# MonoPedal.net
KiCad netlist of a schematic drawn in EAGLE
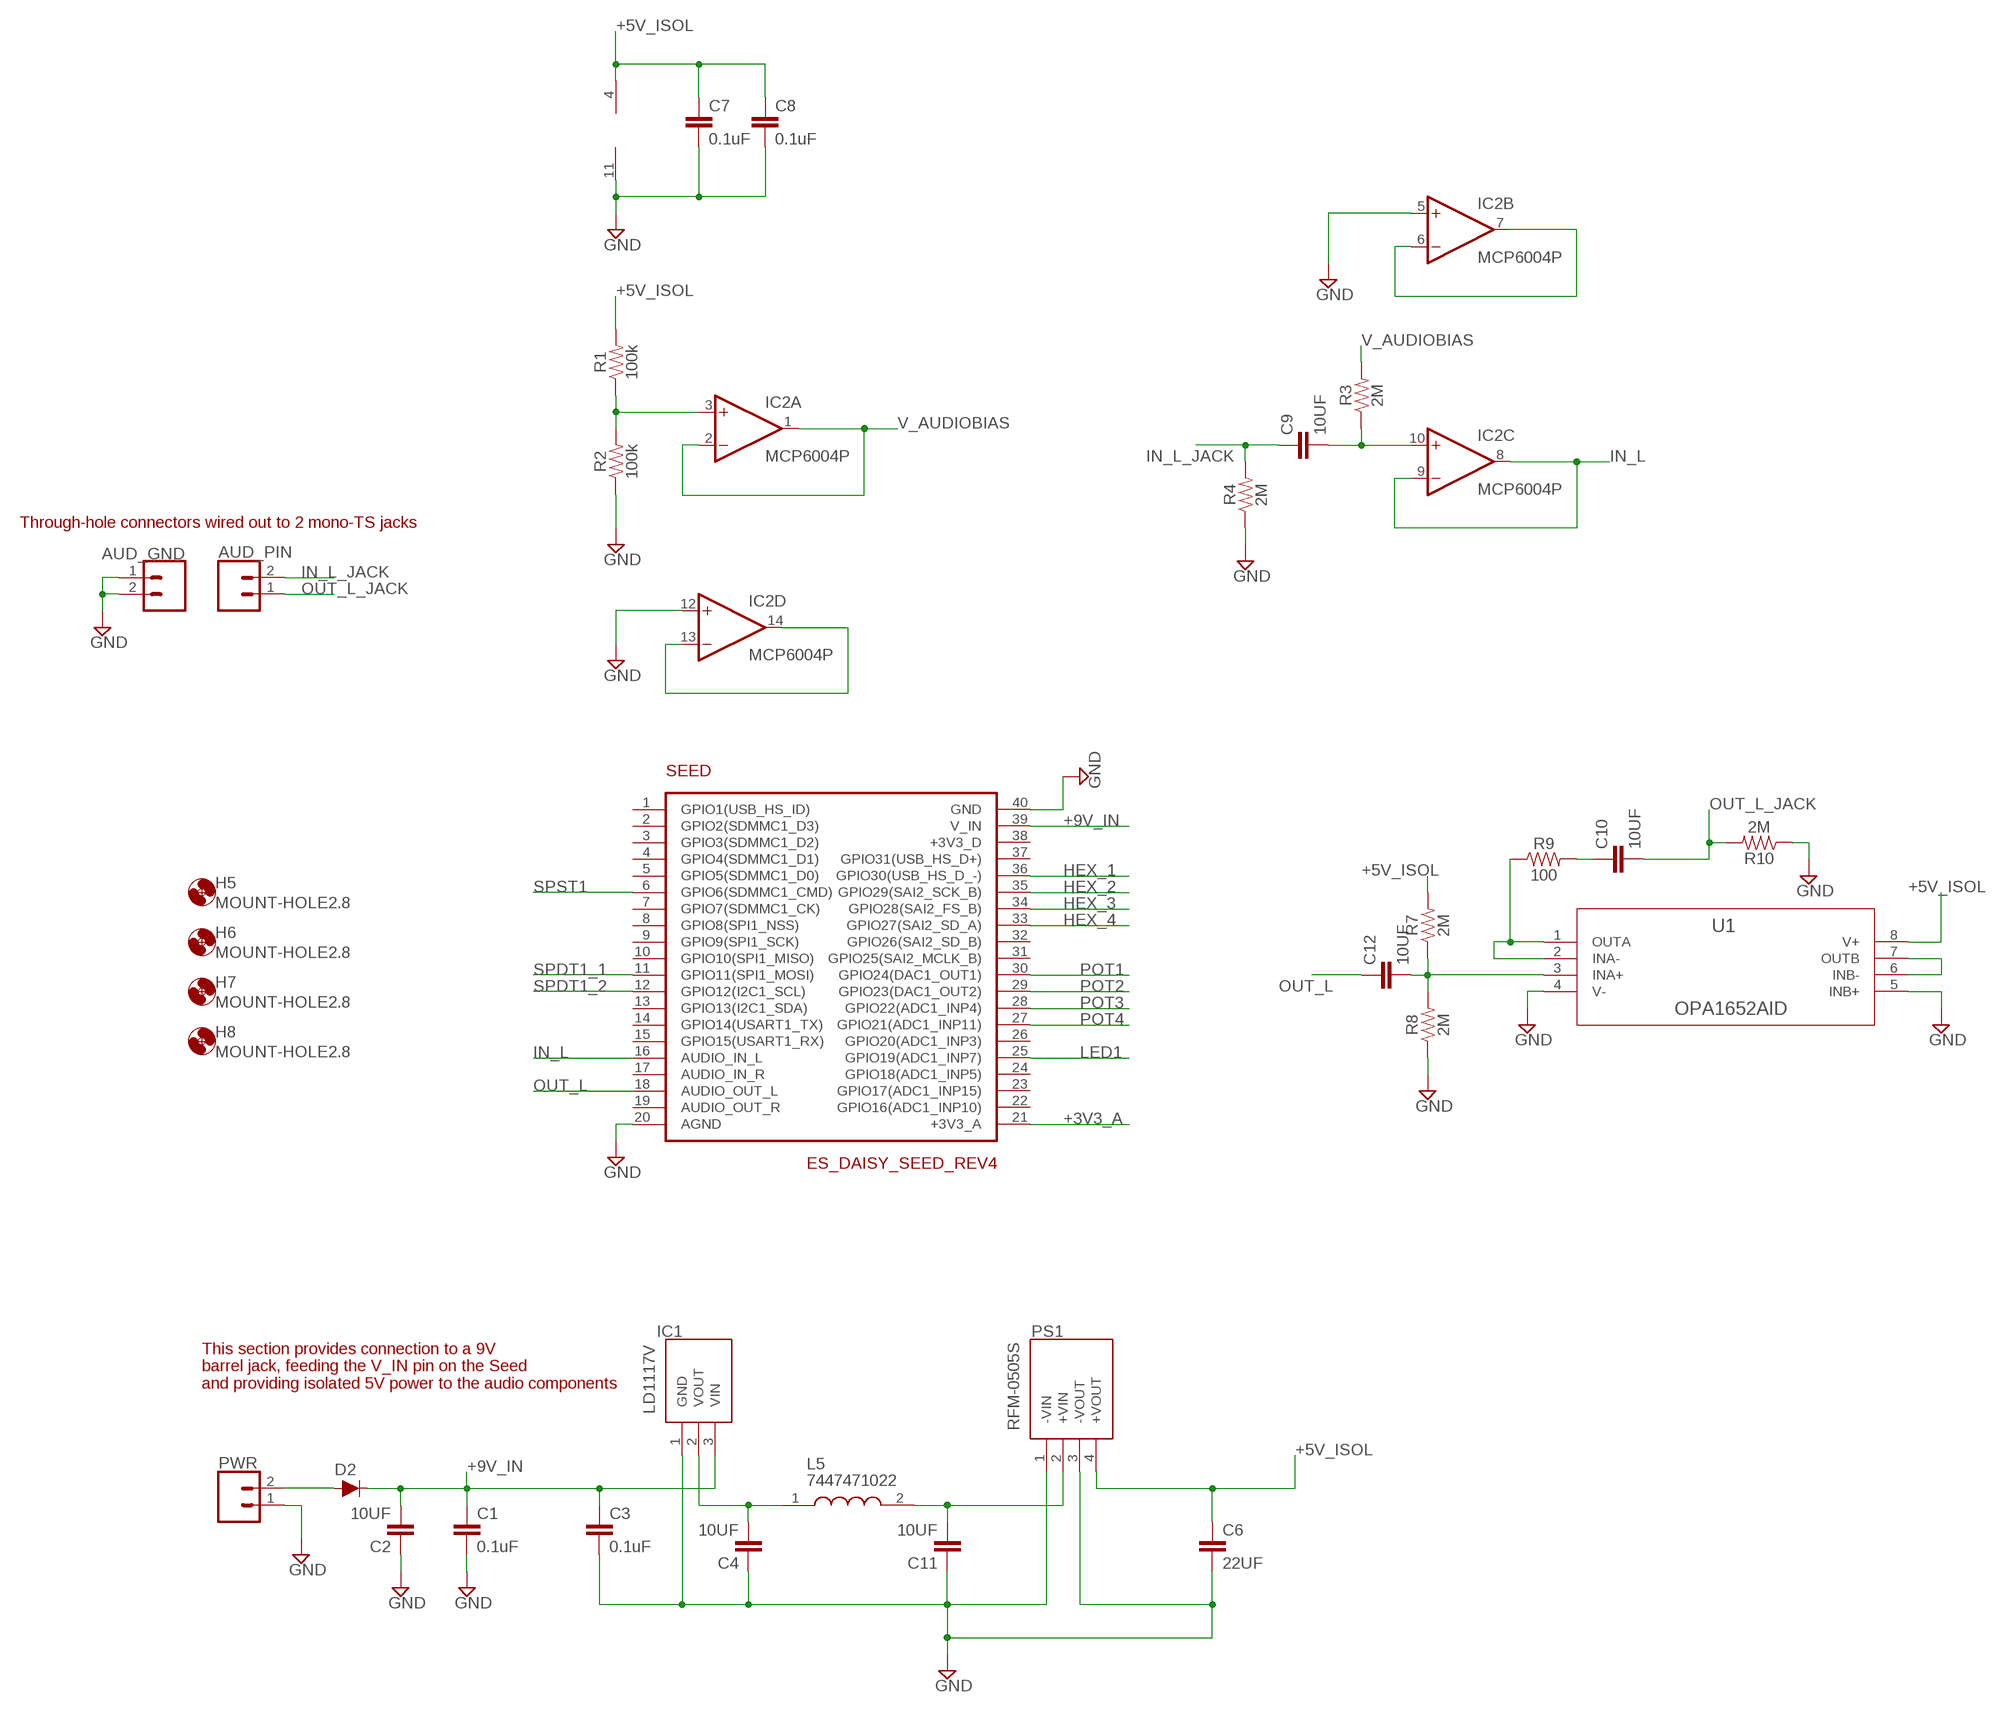
[diagram p0: schematic, sheet 1]
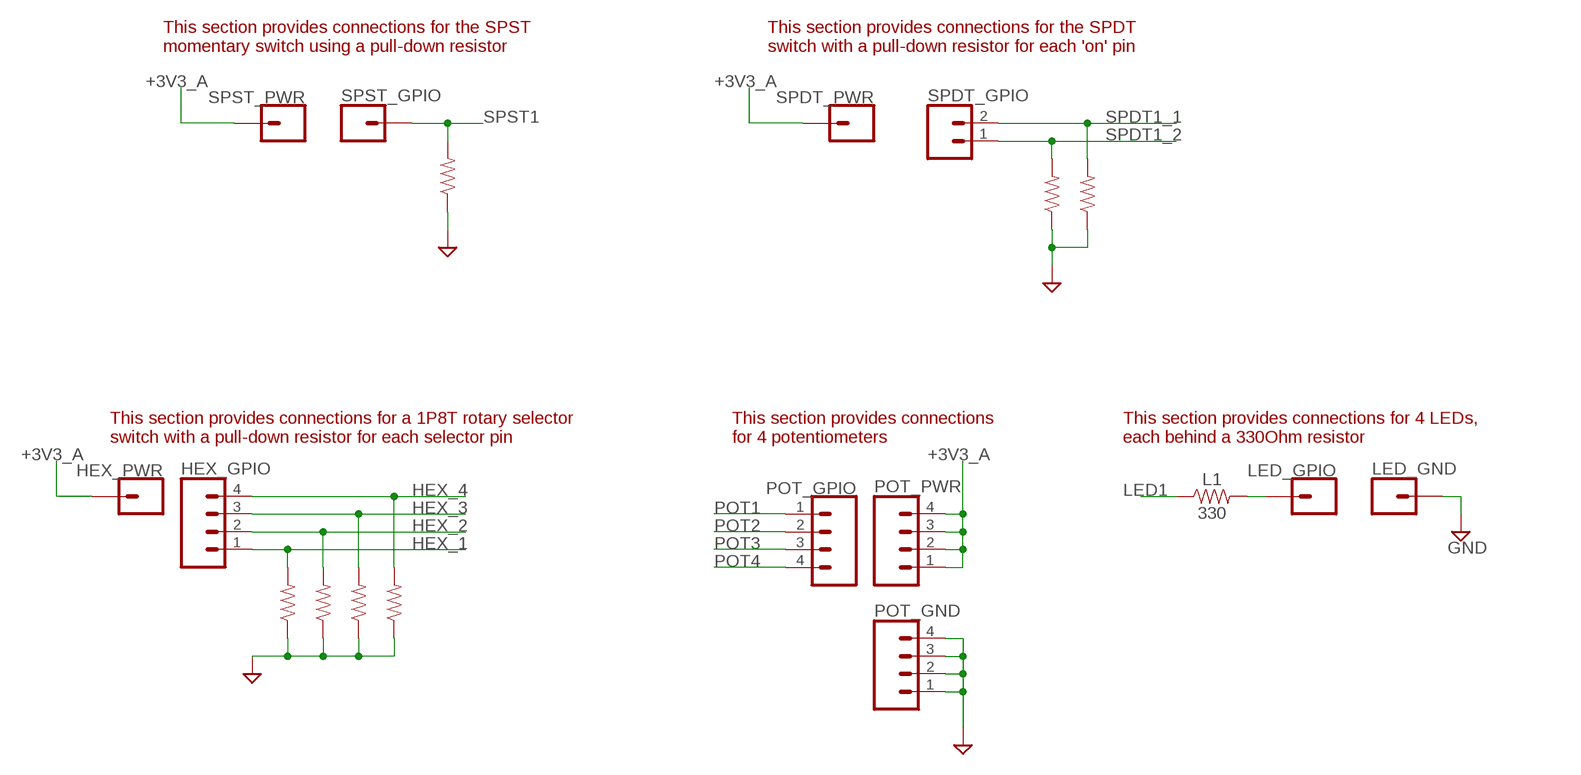
[diagram p1: schematic, sheet 2]

(export (version "E")
  (design (tool "Eeschema 10.0.6"))
  (components
    (comp (ref "AUD_GND")
      (value "CONN_02")
      (footprint "eagle-import:1X02")
      (libsource (lib "eagle-import") (part "CONN_02"))
    )
    (comp (ref "AUD_PIN")
      (value "CONN_02")
      (footprint "eagle-import:1X02")
      (libsource (lib "eagle-import") (part "CONN_02"))
    )
    (comp (ref "C1")
      (value "0.1uF")
      (footprint "eagle-import:CAP-PTH-SMALL-KIT")
      (libsource (lib "eagle-import") (part "0.1UF-KIT-EZ-50V-20%"))
    )
    (comp (ref "C2")
      (value "10UF")
      (footprint "eagle-import:CAP-PTH-SMALL-KIT")
      (libsource (lib "eagle-import") (part "10UF"))
    )
    (comp (ref "C3")
      (value "0.1uF")
      (footprint "eagle-import:CAP-PTH-SMALL-KIT")
      (libsource (lib "eagle-import") (part "0.1UF-KIT-EZ-50V-20%"))
    )
    (comp (ref "C4")
      (value "10UF")
      (footprint "eagle-import:CAP-PTH-SMALL-KIT")
      (libsource (lib "eagle-import") (part "10UF"))
    )
    (comp (ref "C6")
      (value "22UF")
      (footprint "eagle-import:CAP-PTH-SMALL-KIT")
      (libsource (lib "eagle-import") (part "22UF"))
    )
    (comp (ref "C7")
      (value "0.1uF")
      (footprint "eagle-import:CAP-PTH-SMALL-KIT")
      (libsource (lib "eagle-import") (part "0.1UF-KIT-EZ-50V-20%"))
    )
    (comp (ref "C8")
      (value "0.1uF")
      (footprint "eagle-import:CAP-PTH-SMALL-KIT")
      (libsource (lib "eagle-import") (part "0.1UF-KIT-EZ-50V-20%"))
    )
    (comp (ref "C9")
      (value "10UF")
      (footprint "eagle-import:CAP-PTH-SMALL-KIT")
      (libsource (lib "eagle-import") (part "10UF"))
    )
    (comp (ref "C10")
      (value "10UF")
      (footprint "eagle-import:CAP-PTH-SMALL-KIT")
      (libsource (lib "eagle-import") (part "10UF"))
    )
    (comp (ref "C11")
      (value "10UF")
      (footprint "eagle-import:CAP-PTH-SMALL-KIT")
      (libsource (lib "eagle-import") (part "10UF"))
    )
    (comp (ref "C12")
      (value "10UF")
      (footprint "eagle-import:CAP-PTH-SMALL-KIT")
      (libsource (lib "eagle-import") (part "10UF"))
    )
    (comp (ref "D2")
      (value "200mA/100V/1V")
      (footprint "eagle-import:DIODE-1N4148")
      (libsource (lib "eagle-import") (part "DIODE-1N4148"))
    )
    (comp (ref "H5")
      (value "MOUNT-HOLE2.8")
      (footprint "eagle-import:2,8")
      (libsource (lib "eagle-import") (part "MOUNT-HOLE2.8"))
    )
    (comp (ref "H6")
      (value "MOUNT-HOLE2.8")
      (footprint "eagle-import:2,8")
      (libsource (lib "eagle-import") (part "MOUNT-HOLE2.8"))
    )
    (comp (ref "H7")
      (value "MOUNT-HOLE2.8")
      (footprint "eagle-import:2,8")
      (libsource (lib "eagle-import") (part "MOUNT-HOLE2.8"))
    )
    (comp (ref "H8")
      (value "MOUNT-HOLE2.8")
      (footprint "eagle-import:2,8")
      (libsource (lib "eagle-import") (part "MOUNT-HOLE2.8"))
    )
    (comp (ref "IC1")
      (value "LD1117V")
      (footprint "eagle-import:TO255P460X1020X2008-3P")
      (fields (field (name "MOUSER_PART_NUMBER") "511-LD1117V"))
      (libsource (lib "eagle-import") (part "LD1117V"))
    )
    (comp (ref "IC2")
      (value "MCP6004P")
      (footprint "eagle-import:DIL14")
      (libsource (lib "eagle-import") (part "MCP6004P"))
    )
    (comp (ref "L5")
      (value "7447471022")
      (footprint "eagle-import:WE-TIS_111190")
      (fields (field (name "MOUSER_PART_NUMBER") "710-7447471022"))
      (libsource (lib "eagle-import") (part "7447471022"))
    )
    (comp (ref "PS1")
      (value "RFM-0505S")
      (footprint "eagle-import:RFM0505S")
      (fields (field (name "MOUSER_PART_NUMBER") "919-RFM-0505S"))
      (libsource (lib "eagle-import") (part "RFM-0505S"))
    )
    (comp (ref "PWR")
      (value "CONN_02")
      (footprint "eagle-import:1X02")
      (libsource (lib "eagle-import") (part "CONN_02"))
    )
    (comp (ref "R1")
      (value "100k")
      (footprint "eagle-import:AXIAL-0.3")
      (libsource (lib "eagle-import") (part "100KOHM-HORIZ-1/4W-5%"))
    )
    (comp (ref "R2")
      (value "100k")
      (footprint "eagle-import:AXIAL-0.3")
      (libsource (lib "eagle-import") (part "100KOHM-HORIZ-1/4W-5%"))
    )
    (comp (ref "R3")
      (value "2M")
      (footprint "eagle-import:AXIAL-0.3")
      (libsource (lib "eagle-import") (part "2MOHM-HORIZ-1/4W-5%"))
    )
    (comp (ref "R4")
      (value "2M")
      (footprint "eagle-import:AXIAL-0.3")
      (libsource (lib "eagle-import") (part "2MOHM-HORIZ-1/4W-5%"))
    )
    (comp (ref "R7")
      (value "2M")
      (footprint "eagle-import:AXIAL-0.3")
      (libsource (lib "eagle-import") (part "2MOHM-HORIZ-1/4W-5%"))
    )
    (comp (ref "R8")
      (value "2M")
      (footprint "eagle-import:AXIAL-0.3")
      (libsource (lib "eagle-import") (part "2MOHM-HORIZ-1/4W-5%"))
    )
    (comp (ref "R9")
      (value "100")
      (footprint "eagle-import:AXIAL-0.3")
      (libsource (lib "eagle-import") (part "100OHM-HORIZ-1/4W-1%"))
    )
    (comp (ref "R10")
      (value "2M")
      (footprint "eagle-import:AXIAL-0.3")
      (libsource (lib "eagle-import") (part "2MOHM-HORIZ-1/4W-5%"))
    )
    (comp (ref "SEED")
      (value "ES_DAISY_SEED_REV4")
      (footprint "eagle-import:ES_DAISY_SEED")
      (libsource (lib "eagle-import") (part "ES_DAISY_SEED_REV4"))
    )
    (comp (ref "U1")
      (value "OPA1652AID")
      (footprint "eagle-import:D8")
      (fields
        (field (name "GENERIC_PART_NUMBER") "OPA1652")
        (field (name "MANUFACTURER") "Texas Instruments")
      )
      (libsource (lib "eagle-import") (part "OPA1652AID"))
    )
    (comp (ref "D11")
      (value "10k")
      (footprint "eagle-import:AXIAL-0.3")
      (libsource (lib "eagle-import") (part "10KOHM-HORIZ-1/4W-5%"))
    )
    (comp (ref "D12")
      (value "10k")
      (footprint "eagle-import:AXIAL-0.3")
      (libsource (lib "eagle-import") (part "10KOHM-HORIZ-1/4W-5%"))
    )
    (comp (ref "H1")
      (value "10k")
      (footprint "eagle-import:AXIAL-0.3")
      (libsource (lib "eagle-import") (part "10KOHM-HORIZ-1/4W-5%"))
    )
    (comp (ref "H2")
      (value "10k")
      (footprint "eagle-import:AXIAL-0.3")
      (libsource (lib "eagle-import") (part "10KOHM-HORIZ-1/4W-5%"))
    )
    (comp (ref "H3")
      (value "10k")
      (footprint "eagle-import:AXIAL-0.3")
      (libsource (lib "eagle-import") (part "10KOHM-HORIZ-1/4W-5%"))
    )
    (comp (ref "H4")
      (value "10k")
      (footprint "eagle-import:AXIAL-0.3")
      (libsource (lib "eagle-import") (part "10KOHM-HORIZ-1/4W-5%"))
    )
    (comp (ref "HEX_GPIO")
      (value "CONN_04")
      (footprint "eagle-import:1X04")
      (libsource (lib "eagle-import") (part "CONN_04"))
    )
    (comp (ref "HEX_PWR")
      (value "CONN_01")
      (footprint "eagle-import:1X01")
      (libsource (lib "eagle-import") (part "CONN_01"))
    )
    (comp (ref "L1")
      (value "330")
      (footprint "eagle-import:AXIAL-0.3")
      (libsource (lib "eagle-import") (part "330OHM-HORIZ-1/10W-5%"))
    )
    (comp (ref "LED_GND")
      (value "CONN_01")
      (footprint "eagle-import:1X01")
      (libsource (lib "eagle-import") (part "CONN_01"))
    )
    (comp (ref "LED_GPIO")
      (value "CONN_01")
      (footprint "eagle-import:1X01")
      (libsource (lib "eagle-import") (part "CONN_01"))
    )
    (comp (ref "POT_GND")
      (value "CONN_04")
      (footprint "eagle-import:1X04")
      (libsource (lib "eagle-import") (part "CONN_04"))
    )
    (comp (ref "POT_GPIO")
      (value "CONN_04")
      (footprint "eagle-import:1X04")
      (libsource (lib "eagle-import") (part "CONN_04"))
    )
    (comp (ref "POT_PWR")
      (value "CONN_04")
      (footprint "eagle-import:1X04")
      (libsource (lib "eagle-import") (part "CONN_04"))
    )
    (comp (ref "S1")
      (value "10k")
      (footprint "eagle-import:AXIAL-0.3")
      (libsource (lib "eagle-import") (part "10KOHM-HORIZ-1/4W-5%"))
    )
    (comp (ref "SPDT_GPIO")
      (value "CONN_02")
      (footprint "eagle-import:1X02")
      (libsource (lib "eagle-import") (part "CONN_02"))
    )
    (comp (ref "SPDT_PWR")
      (value "CONN_01")
      (footprint "eagle-import:1X01")
      (libsource (lib "eagle-import") (part "CONN_01"))
    )
    (comp (ref "SPST_GPIO")
      (value "CONN_01")
      (footprint "eagle-import:1X01")
      (libsource (lib "eagle-import") (part "CONN_01"))
    )
    (comp (ref "SPST_PWR")
      (value "CONN_01")
      (footprint "eagle-import:1X01")
      (libsource (lib "eagle-import") (part "CONN_01"))
    )
  )
  (nets
    (net (code "1") (name "+3V3_A") (class "Default")
      (node (ref "HEX_PWR") (pin "1") (pinfunction "1_1") (pintype "passive"))
      (node (ref "POT_PWR") (pin "1") (pinfunction "1_1") (pintype "passive"))
      (node (ref "POT_PWR") (pin "2") (pinfunction "2_2") (pintype "passive"))
      (node (ref "POT_PWR") (pin "3") (pinfunction "3_3") (pintype "passive"))
      (node (ref "POT_PWR") (pin "4") (pinfunction "4_4") (pintype "passive"))
      (node (ref "SEED") (pin "21") (pinfunction "+3V3_A_21") (pintype "bidirectional"))
      (node (ref "SPDT_PWR") (pin "1") (pinfunction "1_1") (pintype "passive"))
      (node (ref "SPST_PWR") (pin "1") (pinfunction "1_1") (pintype "passive"))
    )
    (net (code "2") (name "+5V_ISOL") (class "Default")
      (node (ref "C6") (pin "1") (pinfunction "1_1") (pintype "passive"))
      (node (ref "C7") (pin "1") (pinfunction "1_1") (pintype "passive"))
      (node (ref "C8") (pin "1") (pinfunction "1_1") (pintype "passive"))
      (node (ref "IC2") (pin "4") (pinfunction "V+_4") (pintype "power_in"))
      (node (ref "PS1") (pin "4") (pinfunction "+VOUT_4") (pintype "bidirectional"))
      (node (ref "R1") (pin "P$2") (pinfunction "2_P$2") (pintype "passive"))
      (node (ref "R7") (pin "P$2") (pinfunction "2_P$2") (pintype "passive"))
      (node (ref "U1") (pin "8") (pinfunction "V+_8") (pintype "power_in"))
    )
    (net (code "3") (name "+9V_IN") (class "Default")
      (node (ref "C1") (pin "1") (pinfunction "1_1") (pintype "passive"))
      (node (ref "C2") (pin "2") (pinfunction "2_2") (pintype "passive"))
      (node (ref "C3") (pin "1") (pinfunction "1_1") (pintype "passive"))
      (node (ref "D2") (pin "C") (pinfunction "C_C") (pintype "passive"))
      (node (ref "IC1") (pin "3") (pinfunction "VIN_3") (pintype "bidirectional"))
      (node (ref "SEED") (pin "39") (pinfunction "V_IN_39") (pintype "bidirectional"))
    )
    (net (code "4") (name "GND") (class "Default")
      (node (ref "AUD_GND") (pin "1") (pinfunction "1_1") (pintype "passive"))
      (node (ref "AUD_GND") (pin "2") (pinfunction "2_2") (pintype "passive"))
      (node (ref "C1") (pin "2") (pinfunction "2_2") (pintype "passive"))
      (node (ref "C11") (pin "1") (pinfunction "1_1") (pintype "passive"))
      (node (ref "C2") (pin "1") (pinfunction "1_1") (pintype "passive"))
      (node (ref "C3") (pin "2") (pinfunction "2_2") (pintype "passive"))
      (node (ref "C4") (pin "1") (pinfunction "1_1") (pintype "passive"))
      (node (ref "C6") (pin "2") (pinfunction "2_2") (pintype "passive"))
      (node (ref "C7") (pin "2") (pinfunction "2_2") (pintype "passive"))
      (node (ref "C8") (pin "2") (pinfunction "2_2") (pintype "passive"))
      (node (ref "D11") (pin "P$1") (pinfunction "1_P$1") (pintype "passive"))
      (node (ref "D12") (pin "P$1") (pinfunction "1_P$1") (pintype "passive"))
      (node (ref "H1") (pin "P$1") (pinfunction "1_P$1") (pintype "passive"))
      (node (ref "H2") (pin "P$1") (pinfunction "1_P$1") (pintype "passive"))
      (node (ref "H3") (pin "P$1") (pinfunction "1_P$1") (pintype "passive"))
      (node (ref "H4") (pin "P$1") (pinfunction "1_P$1") (pintype "passive"))
      (node (ref "IC1") (pin "1") (pinfunction "GND_1") (pintype "bidirectional"))
      (node (ref "IC2") (pin "11") (pinfunction "V-_11") (pintype "power_in"))
      (node (ref "IC2") (pin "12") (pinfunction "+IN_12") (pintype "input"))
      (node (ref "IC2") (pin "5") (pinfunction "+IN_5") (pintype "input"))
      (node (ref "LED_GND") (pin "1") (pinfunction "1_1") (pintype "passive"))
      (node (ref "POT_GND") (pin "1") (pinfunction "1_1") (pintype "passive"))
      (node (ref "POT_GND") (pin "2") (pinfunction "2_2") (pintype "passive"))
      (node (ref "POT_GND") (pin "3") (pinfunction "3_3") (pintype "passive"))
      (node (ref "POT_GND") (pin "4") (pinfunction "4_4") (pintype "passive"))
      (node (ref "PS1") (pin "1") (pinfunction "-VIN_1") (pintype "bidirectional"))
      (node (ref "PS1") (pin "3") (pinfunction "-VOUT_3") (pintype "bidirectional"))
      (node (ref "PWR") (pin "1") (pinfunction "1_1") (pintype "passive"))
      (node (ref "R10") (pin "P$1") (pinfunction "1_P$1") (pintype "passive"))
      (node (ref "R2") (pin "P$1") (pinfunction "1_P$1") (pintype "passive"))
      (node (ref "R4") (pin "P$1") (pinfunction "1_P$1") (pintype "passive"))
      (node (ref "R8") (pin "P$1") (pinfunction "1_P$1") (pintype "passive"))
      (node (ref "S1") (pin "P$1") (pinfunction "1_P$1") (pintype "passive"))
      (node (ref "SEED") (pin "20") (pinfunction "AGND_20") (pintype "bidirectional"))
      (node (ref "SEED") (pin "40") (pinfunction "GND_40") (pintype "bidirectional"))
      (node (ref "U1") (pin "4") (pinfunction "V-_4") (pintype "power_in"))
      (node (ref "U1") (pin "5") (pinfunction "INB+_5") (pintype "input"))
    )
    (net (code "5") (name "HEX_1") (class "Default")
      (node (ref "H1") (pin "P$2") (pinfunction "2_P$2") (pintype "passive"))
      (node (ref "HEX_GPIO") (pin "1") (pinfunction "1_1") (pintype "passive"))
      (node (ref "SEED") (pin "36") (pinfunction "GPIO30(USB_HS_D_-)_36") (pintype "bidirectional"))
    )
    (net (code "6") (name "HEX_2") (class "Default")
      (node (ref "H2") (pin "P$2") (pinfunction "2_P$2") (pintype "passive"))
      (node (ref "HEX_GPIO") (pin "2") (pinfunction "2_2") (pintype "passive"))
      (node (ref "SEED") (pin "35") (pinfunction "GPIO29(SAI2_SCK_B)_35") (pintype "bidirectional"))
    )
    (net (code "7") (name "HEX_3") (class "Default")
      (node (ref "H3") (pin "P$2") (pinfunction "2_P$2") (pintype "passive"))
      (node (ref "HEX_GPIO") (pin "3") (pinfunction "3_3") (pintype "passive"))
      (node (ref "SEED") (pin "34") (pinfunction "GPIO28(SAI2_FS_B)_34") (pintype "bidirectional"))
    )
    (net (code "8") (name "HEX_4") (class "Default")
      (node (ref "H4") (pin "P$2") (pinfunction "2_P$2") (pintype "passive"))
      (node (ref "HEX_GPIO") (pin "4") (pinfunction "4_4") (pintype "passive"))
      (node (ref "SEED") (pin "33") (pinfunction "GPIO27(SAI2_SD_A)_33") (pintype "bidirectional"))
    )
    (net (code "9") (name "IN_L") (class "Default")
      (node (ref "IC2") (pin "8") (pinfunction "OUT_8") (pintype "output"))
      (node (ref "IC2") (pin "9") (pinfunction "-IN_9") (pintype "input"))
      (node (ref "SEED") (pin "16") (pinfunction "AUDIO_IN_L_16") (pintype "bidirectional"))
    )
    (net (code "10") (name "IN_L_JACK") (class "Default")
      (node (ref "AUD_PIN") (pin "2") (pinfunction "2_2") (pintype "passive"))
      (node (ref "C9") (pin "1") (pinfunction "1_1") (pintype "passive"))
      (node (ref "R4") (pin "P$2") (pinfunction "2_P$2") (pintype "passive"))
    )
    (net (code "11") (name "LED1") (class "Default")
      (node (ref "L1") (pin "P$1") (pinfunction "1_P$1") (pintype "passive"))
      (node (ref "SEED") (pin "25") (pinfunction "GPIO19(ADC1_INP7)_25") (pintype "bidirectional"))
    )
    (net (code "12") (name "Net-(D2-PadA)") (class "Default")
      (node (ref "D2") (pin "A") (pinfunction "A_A") (pintype "passive"))
      (node (ref "PWR") (pin "2") (pinfunction "2_2") (pintype "passive"))
    )
    (net (code "13") (name "Net-(IC1-VOUT)") (class "Default")
      (node (ref "C4") (pin "2") (pinfunction "2_2") (pintype "passive"))
      (node (ref "IC1") (pin "2") (pinfunction "VOUT_2") (pintype "bidirectional"))
      (node (ref "L5") (pin "1") (pinfunction "1_1") (pintype "bidirectional"))
    )
    (net (code "14") (name "Net-(IC2A-+IN)") (class "Default")
      (node (ref "IC2") (pin "3") (pinfunction "+IN_3") (pintype "input"))
      (node (ref "R1") (pin "P$1") (pinfunction "1_P$1") (pintype "passive"))
      (node (ref "R2") (pin "P$2") (pinfunction "2_P$2") (pintype "passive"))
    )
    (net (code "15") (name "Net-(IC2B--IN)") (class "Default")
      (node (ref "IC2") (pin "6") (pinfunction "-IN_6") (pintype "input"))
      (node (ref "IC2") (pin "7") (pinfunction "OUT_7") (pintype "output"))
    )
    (net (code "16") (name "Net-(IC2C-+IN)") (class "Default")
      (node (ref "C9") (pin "2") (pinfunction "2_2") (pintype "passive"))
      (node (ref "IC2") (pin "10") (pinfunction "+IN_10") (pintype "input"))
      (node (ref "R3") (pin "P$1") (pinfunction "1_P$1") (pintype "passive"))
    )
    (net (code "17") (name "Net-(IC2D--IN)") (class "Default")
      (node (ref "IC2") (pin "13") (pinfunction "-IN_13") (pintype "input"))
      (node (ref "IC2") (pin "14") (pinfunction "OUT_14") (pintype "output"))
    )
    (net (code "18") (name "Net-(L1-2)") (class "Default")
      (node (ref "L1") (pin "P$2") (pinfunction "2_P$2") (pintype "passive"))
      (node (ref "LED_GPIO") (pin "1") (pinfunction "1_1") (pintype "passive"))
    )
    (net (code "19") (name "Net-(PS1-+VIN)") (class "Default")
      (node (ref "C11") (pin "2") (pinfunction "2_2") (pintype "passive"))
      (node (ref "L5") (pin "2") (pinfunction "2_2") (pintype "bidirectional"))
      (node (ref "PS1") (pin "2") (pinfunction "+VIN_2") (pintype "bidirectional"))
    )
    (net (code "20") (name "Net-(R7-1)") (class "Default")
      (node (ref "C12") (pin "2") (pinfunction "2_2") (pintype "passive"))
      (node (ref "R7") (pin "P$1") (pinfunction "1_P$1") (pintype "passive"))
      (node (ref "R8") (pin "P$2") (pinfunction "2_P$2") (pintype "passive"))
      (node (ref "U1") (pin "3") (pinfunction "INA+_3") (pintype "input"))
    )
    (net (code "21") (name "Net-(R9-1)") (class "Default")
      (node (ref "R9") (pin "P$1") (pinfunction "1_P$1") (pintype "passive"))
      (node (ref "U1") (pin "1") (pinfunction "OUTA_1") (pintype "output"))
      (node (ref "U1") (pin "2") (pinfunction "INA-_2") (pintype "input"))
    )
    (net (code "22") (name "Net-(R9-2)") (class "Default")
      (node (ref "C10") (pin "1") (pinfunction "1_1") (pintype "passive"))
      (node (ref "R9") (pin "P$2") (pinfunction "2_P$2") (pintype "passive"))
    )
    (net (code "23") (name "Net-(U1-INB-)") (class "Default")
      (node (ref "U1") (pin "6") (pinfunction "INB-_6") (pintype "input"))
      (node (ref "U1") (pin "7") (pinfunction "OUTB_7") (pintype "output"))
    )
    (net (code "24") (name "OUT_L") (class "Default")
      (node (ref "C12") (pin "1") (pinfunction "1_1") (pintype "passive"))
      (node (ref "SEED") (pin "18") (pinfunction "AUDIO_OUT_L_18") (pintype "bidirectional"))
    )
    (net (code "25") (name "OUT_L_JACK") (class "Default")
      (node (ref "AUD_PIN") (pin "1") (pinfunction "1_1") (pintype "passive"))
      (node (ref "C10") (pin "2") (pinfunction "2_2") (pintype "passive"))
      (node (ref "R10") (pin "P$2") (pinfunction "2_P$2") (pintype "passive"))
    )
    (net (code "26") (name "POT1") (class "Default")
      (node (ref "POT_GPIO") (pin "1") (pinfunction "1_1") (pintype "passive"))
      (node (ref "SEED") (pin "30") (pinfunction "GPIO24(DAC1_OUT1)_30") (pintype "bidirectional"))
    )
    (net (code "27") (name "POT2") (class "Default")
      (node (ref "POT_GPIO") (pin "2") (pinfunction "2_2") (pintype "passive"))
      (node (ref "SEED") (pin "29") (pinfunction "GPIO23(DAC1_OUT2)_29") (pintype "bidirectional"))
    )
    (net (code "28") (name "POT3") (class "Default")
      (node (ref "POT_GPIO") (pin "3") (pinfunction "3_3") (pintype "passive"))
      (node (ref "SEED") (pin "28") (pinfunction "GPIO22(ADC1_INP4)_28") (pintype "bidirectional"))
    )
    (net (code "29") (name "POT4") (class "Default")
      (node (ref "POT_GPIO") (pin "4") (pinfunction "4_4") (pintype "passive"))
      (node (ref "SEED") (pin "27") (pinfunction "GPIO21(ADC1_INP11)_27") (pintype "bidirectional"))
    )
    (net (code "30") (name "SPDT1_1") (class "Default")
      (node (ref "D11") (pin "P$2") (pinfunction "2_P$2") (pintype "passive"))
      (node (ref "SEED") (pin "11") (pinfunction "GPIO11(SPI1_MOSI)_11") (pintype "bidirectional"))
      (node (ref "SPDT_GPIO") (pin "2") (pinfunction "2_2") (pintype "passive"))
    )
    (net (code "31") (name "SPDT1_2") (class "Default")
      (node (ref "D12") (pin "P$2") (pinfunction "2_P$2") (pintype "passive"))
      (node (ref "SEED") (pin "12") (pinfunction "GPIO12(I2C1_SCL)_12") (pintype "bidirectional"))
      (node (ref "SPDT_GPIO") (pin "1") (pinfunction "1_1") (pintype "passive"))
    )
    (net (code "32") (name "SPST1") (class "Default")
      (node (ref "S1") (pin "P$2") (pinfunction "2_P$2") (pintype "passive"))
      (node (ref "SEED") (pin "6") (pinfunction "GPIO6(SDMMC1_CMD)_6") (pintype "bidirectional"))
      (node (ref "SPST_GPIO") (pin "1") (pinfunction "1_1") (pintype "passive"))
    )
    (net (code "33") (name "V_AUDIOBIAS") (class "Default")
      (node (ref "IC2") (pin "1") (pinfunction "OUT_1") (pintype "output"))
      (node (ref "IC2") (pin "2") (pinfunction "-IN_2") (pintype "input"))
      (node (ref "R3") (pin "P$2") (pinfunction "2_P$2") (pintype "passive"))
    )
    (net (code "34") (name "unconnected-(SEED-+3V3_D-Pad38)") (class "Default")
      (node (ref "SEED") (pin "38") (pinfunction "+3V3_D_38") (pintype "bidirectional"))
    )
    (net (code "35") (name "unconnected-(SEED-AUDIO_IN_R-Pad17)") (class "Default")
      (node (ref "SEED") (pin "17") (pinfunction "AUDIO_IN_R_17") (pintype "bidirectional"))
    )
    (net (code "36") (name "unconnected-(SEED-AUDIO_OUT_R-Pad19)") (class "Default")
      (node (ref "SEED") (pin "19") (pinfunction "AUDIO_OUT_R_19") (pintype "bidirectional"))
    )
    (net (code "37") (name "unconnected-(SEED-GPIO1(USB_HS_ID)-Pad1)") (class "Default")
      (node (ref "SEED") (pin "1") (pinfunction "GPIO1(USB_HS_ID)_1") (pintype "bidirectional"))
    )
    (net (code "38") (name "unconnected-(SEED-GPIO2(SDMMC1_D3)-Pad2)") (class "Default")
      (node (ref "SEED") (pin "2") (pinfunction "GPIO2(SDMMC1_D3)_2") (pintype "bidirectional"))
    )
    (net (code "39") (name "unconnected-(SEED-GPIO3(SDMMC1_D2)-Pad3)") (class "Default")
      (node (ref "SEED") (pin "3") (pinfunction "GPIO3(SDMMC1_D2)_3") (pintype "bidirectional"))
    )
    (net (code "40") (name "unconnected-(SEED-GPIO4(SDMMC1_D1)-Pad4)") (class "Default")
      (node (ref "SEED") (pin "4") (pinfunction "GPIO4(SDMMC1_D1)_4") (pintype "bidirectional"))
    )
    (net (code "41") (name "unconnected-(SEED-GPIO5(SDMMC1_D0)-Pad5)") (class "Default")
      (node (ref "SEED") (pin "5") (pinfunction "GPIO5(SDMMC1_D0)_5") (pintype "bidirectional"))
    )
    (net (code "42") (name "unconnected-(SEED-GPIO7(SDMMC1_CK)-Pad7)") (class "Default")
      (node (ref "SEED") (pin "7") (pinfunction "GPIO7(SDMMC1_CK)_7") (pintype "bidirectional"))
    )
    (net (code "43") (name "unconnected-(SEED-GPIO8(SPI1_NSS)-Pad8)") (class "Default")
      (node (ref "SEED") (pin "8") (pinfunction "GPIO8(SPI1_NSS)_8") (pintype "bidirectional"))
    )
    (net (code "44") (name "unconnected-(SEED-GPIO9(SPI1_SCK)-Pad9)") (class "Default")
      (node (ref "SEED") (pin "9") (pinfunction "GPIO9(SPI1_SCK)_9") (pintype "bidirectional"))
    )
    (net (code "45") (name "unconnected-(SEED-GPIO10(SPI1_MISO)-Pad10)") (class "Default")
      (node (ref "SEED") (pin "10") (pinfunction "GPIO10(SPI1_MISO)_10") (pintype "bidirectional"))
    )
    (net (code "46") (name "unconnected-(SEED-GPIO13(I2C1_SDA)-Pad13)") (class "Default")
      (node (ref "SEED") (pin "13") (pinfunction "GPIO13(I2C1_SDA)_13") (pintype "bidirectional"))
    )
    (net (code "47") (name "unconnected-(SEED-GPIO14(USART1_TX)-Pad14)") (class "Default")
      (node (ref "SEED") (pin "14") (pinfunction "GPIO14(USART1_TX)_14") (pintype "bidirectional"))
    )
    (net (code "48") (name "unconnected-(SEED-GPIO15(USART1_RX)-Pad15)") (class "Default")
      (node (ref "SEED") (pin "15") (pinfunction "GPIO15(USART1_RX)_15") (pintype "bidirectional"))
    )
    (net (code "49") (name "unconnected-(SEED-GPIO16(ADC1_INP10)-Pad22)") (class "Default")
      (node (ref "SEED") (pin "22") (pinfunction "GPIO16(ADC1_INP10)_22") (pintype "bidirectional"))
    )
    (net (code "50") (name "unconnected-(SEED-GPIO17(ADC1_INP15)-Pad23)") (class "Default")
      (node (ref "SEED") (pin "23") (pinfunction "GPIO17(ADC1_INP15)_23") (pintype "bidirectional"))
    )
    (net (code "51") (name "unconnected-(SEED-GPIO18(ADC1_INP5)-Pad24)") (class "Default")
      (node (ref "SEED") (pin "24") (pinfunction "GPIO18(ADC1_INP5)_24") (pintype "bidirectional"))
    )
    (net (code "52") (name "unconnected-(SEED-GPIO20(ADC1_INP3)-Pad26)") (class "Default")
      (node (ref "SEED") (pin "26") (pinfunction "GPIO20(ADC1_INP3)_26") (pintype "bidirectional"))
    )
    (net (code "53") (name "unconnected-(SEED-GPIO25(SAI2_MCLK_B)-Pad31)") (class "Default")
      (node (ref "SEED") (pin "31") (pinfunction "GPIO25(SAI2_MCLK_B)_31") (pintype "bidirectional"))
    )
    (net (code "54") (name "unconnected-(SEED-GPIO26(SAI2_SD_B)-Pad32)") (class "Default")
      (node (ref "SEED") (pin "32") (pinfunction "GPIO26(SAI2_SD_B)_32") (pintype "bidirectional"))
    )
    (net (code "55") (name "unconnected-(SEED-GPIO31(USB_HS_D+)-Pad37)") (class "Default")
      (node (ref "SEED") (pin "37") (pinfunction "GPIO31(USB_HS_D+)_37") (pintype "bidirectional"))
    )
  )
)
